# test1.net
KiCad netlist of a schematic drawn in Altium Designer
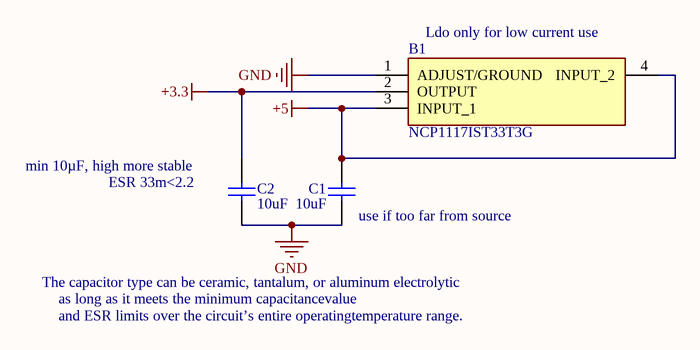
[diagram p0: test1.SchDoc]

(export (version "E")
  (design (tool "Eeschema 10.0.6"))
  (components
    (comp (ref "B1")
      (value "NCP1117IST33T3G")
      (footprint "SOT230P700X180-4N")
      (description "Linear Voltage Regulator IC Positive Fixed 1 Output 1A SOT-223")
      (fields (field (name "MOUSER PART NUMBER") "863-NCP1117IST33T3G"))
      (libsource (lib "Pega Kwan") (part "NCP1117IST33T3G"))
    )
    (comp (ref "C1")
      (value "10uF")
      (footprint "0603_SMD_RC")
      (description "SMD 0603 Capacitor")
      (libsource (lib "05E_ShareComponentLibrary") (part "SMD 0603 Capacitor"))
    )
    (comp (ref "C2")
      (value "10uF")
      (footprint "0603_SMD_RC")
      (description "SMD 0603 Capacitor")
      (libsource (lib "05E_ShareComponentLibrary") (part "SMD 0603 Capacitor"))
    )
  )
  (nets
    (net (code "1") (name "+3.3") (class "Default")
      (node (ref "B1") (pin "2") (pinfunction "OUTPUT_2") (pintype "passive"))
      (node (ref "C2") (pin "2") (pinfunction "2_2") (pintype "passive"))
    )
    (net (code "2") (name "+5") (class "Default")
      (node (ref "B1") (pin "3") (pinfunction "INPUT_1_3") (pintype "passive"))
      (node (ref "B1") (pin "4") (pinfunction "INPUT_2_4") (pintype "passive"))
      (node (ref "C1") (pin "2") (pinfunction "2_2") (pintype "passive"))
    )
    (net (code "3") (name "GND") (class "Default")
      (node (ref "B1") (pin "1") (pinfunction "ADJUST/GROUND_1") (pintype "passive"))
      (node (ref "C1") (pin "1") (pinfunction "1_1") (pintype "passive"))
      (node (ref "C2") (pin "1") (pinfunction "1_1") (pintype "passive"))
    )
  )
)
